# isolation-alt.net
KiCad netlist of a schematic drawn in Altium Designer
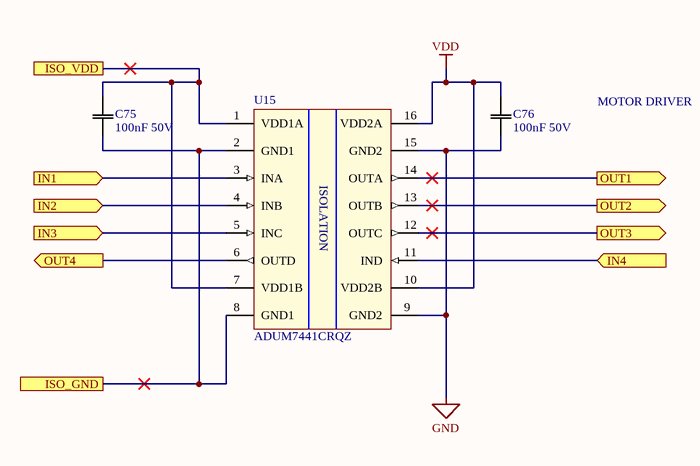
[diagram p0: isolation-alt.SchDoc]

(export (version "E")
  (design (tool "Eeschema 10.0.6"))
  (components
    (comp (ref "C75")
      (value "100nF 50V")
      (footprint "0603")
      (description "Default Symbol for Capacitors")
      (fields (field (name "PART NUMBER") "CAP 100nF 50V") (field (name "TOLERANCE") "10%"))
      (libsource (lib "capacitor_library") (part "CAP_Default"))
    )
    (comp (ref "C76")
      (value "100nF 50V")
      (footprint "0603")
      (description "Default Symbol for Capacitors")
      (fields (field (name "PART NUMBER") "CAP 100nF 50V") (field (name "TOLERANCE") "10%"))
      (libsource (lib "capacitor_library") (part "CAP_Default"))
    )
    (comp (ref "U15")
      (value "ADUM7441CRQZ")
      (footprint "SOP64P600X175-16N")
      (description "Digital Isolator CMOS 4-CH 150Mbps 16-Pin QSOP T/R")
      (fields (field (name "PART NUMBER") "ISO ADUM7441CRQZ"))
      (libsource (lib "IC_Library") (part "ISO ADUM7441CRQZ"))
    )
  )
  (nets
    (net (code "1") (name "/IN1") (class "Default")
      (node (ref "U15") (pin "3") (pinfunction "INA_3") (pintype "input"))
    )
    (net (code "2") (name "/IN2") (class "Default")
      (node (ref "U15") (pin "4") (pinfunction "INB_4") (pintype "input"))
    )
    (net (code "3") (name "/IN3") (class "Default")
      (node (ref "U15") (pin "5") (pinfunction "INC_5") (pintype "input"))
    )
    (net (code "4") (name "/IN4") (class "Default")
      (node (ref "U15") (pin "11") (pinfunction "IND_11") (pintype "input"))
    )
    (net (code "5") (name "/ISO_GND") (class "Default")
      (node (ref "C75") (pin "1") (pinfunction "C1_1") (pintype "passive"))
      (node (ref "U15") (pin "2") (pinfunction "GND1_2") (pintype "power_in"))
      (node (ref "U15") (pin "8") (pinfunction "GND1_8") (pintype "power_in"))
    )
    (net (code "6") (name "/ISO_VDD") (class "Default")
      (node (ref "C75") (pin "2") (pinfunction "C2_2") (pintype "passive"))
      (node (ref "U15") (pin "1") (pinfunction "VDD1A_1") (pintype "power_in"))
      (node (ref "U15") (pin "7") (pinfunction "VDD1B_7") (pintype "passive"))
    )
    (net (code "7") (name "/OUT1") (class "Default")
      (node (ref "U15") (pin "14") (pinfunction "OUTA_14") (pintype "output"))
    )
    (net (code "8") (name "/OUT2") (class "Default")
      (node (ref "U15") (pin "13") (pinfunction "OUTB_13") (pintype "output"))
    )
    (net (code "9") (name "/OUT3") (class "Default")
      (node (ref "U15") (pin "12") (pinfunction "OUTC_12") (pintype "output"))
    )
    (net (code "10") (name "/OUT4") (class "Default")
      (node (ref "U15") (pin "6") (pinfunction "OUTD_6") (pintype "output"))
    )
    (net (code "11") (name "GND") (class "Default")
      (node (ref "C76") (pin "1") (pinfunction "C1_1") (pintype "passive"))
      (node (ref "U15") (pin "15") (pinfunction "GND2_15") (pintype "power_in"))
      (node (ref "U15") (pin "9") (pinfunction "GND2_9") (pintype "power_in"))
    )
    (net (code "12") (name "VDD") (class "Default")
      (node (ref "C76") (pin "2") (pinfunction "C2_2") (pintype "passive"))
      (node (ref "U15") (pin "10") (pinfunction "VDD2B_10") (pintype "passive"))
      (node (ref "U15") (pin "16") (pinfunction "VDD2A_16") (pintype "power_in"))
    )
  )
)
